# Pipe_flow_header_v3.net
KiCad netlist of a schematic drawn in EAGLE
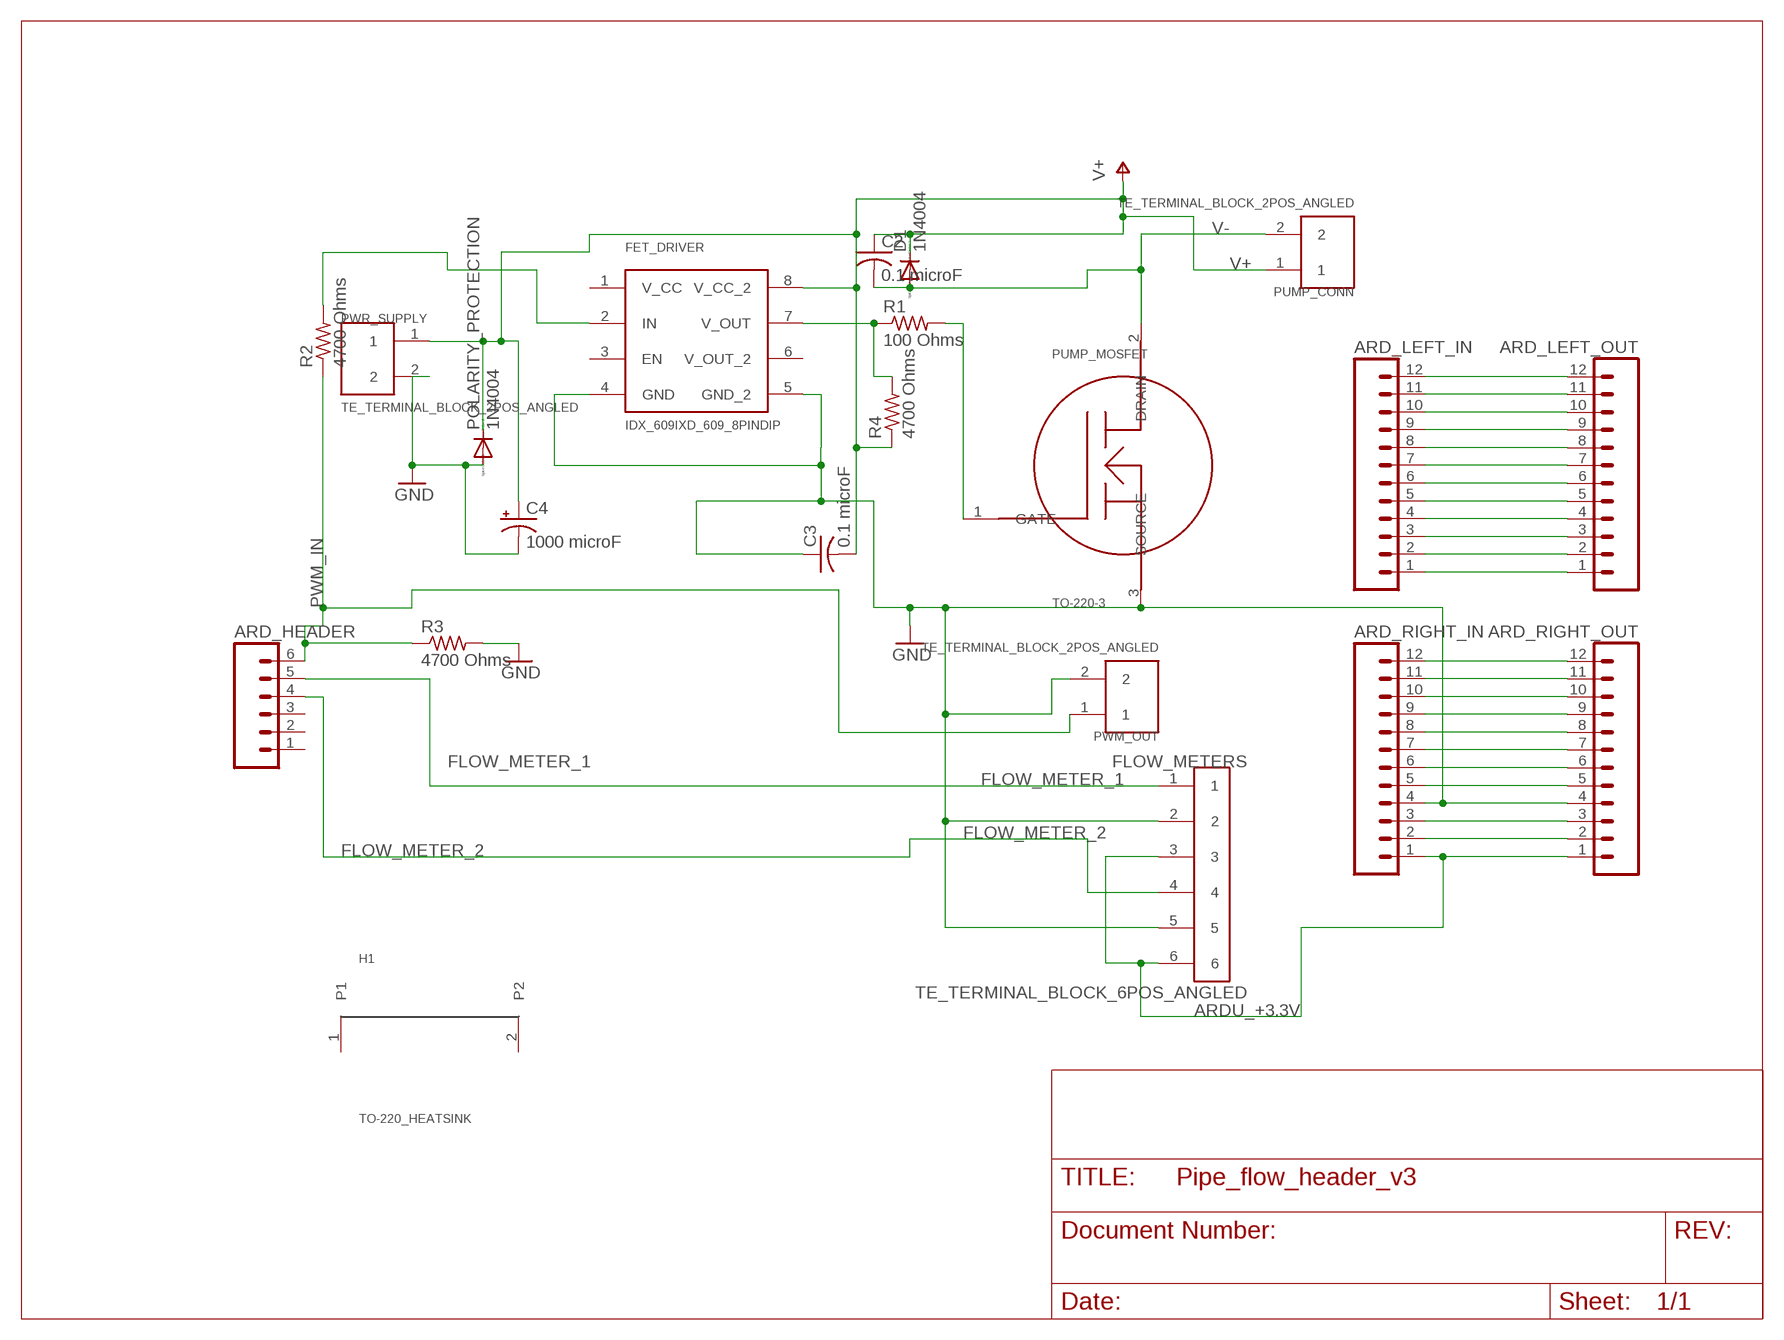
[diagram p0: schematic, sheet 1]

(export (version "E")
  (design (tool "Eeschema 10.0.6"))
  (components
    (comp (ref "ARD_HEADER")
      (value "M06LONGPADS")
      (footprint "eagle-import:1X06_LONGPADS")
      (libsource (lib "eagle-import") (part "M06LONGPADS"))
    )
    (comp (ref "ARD_LEFT_IN")
      (value "M12LOCK_LONGPADS")
      (footprint "eagle-import:1X12_LOCK_LONGPADS")
      (libsource (lib "eagle-import") (part "M12LOCK_LONGPADS"))
    )
    (comp (ref "ARD_LEFT_OUT")
      (value "M12LOCK_LONGPADS")
      (footprint "eagle-import:1X12_LOCK_LONGPADS")
      (libsource (lib "eagle-import") (part "M12LOCK_LONGPADS"))
    )
    (comp (ref "ARD_RIGHT_IN")
      (value "M12LOCK_LONGPADS")
      (footprint "eagle-import:1X12_LOCK_LONGPADS")
      (libsource (lib "eagle-import") (part "M12LOCK_LONGPADS"))
    )
    (comp (ref "ARD_RIGHT_OUT")
      (value "M12LOCK_LONGPADS")
      (footprint "eagle-import:1X12_LOCK_LONGPADS")
      (libsource (lib "eagle-import") (part "M12LOCK_LONGPADS"))
    )
    (comp (ref "C2")
      (value "0.1 microF")
      (footprint "eagle-import:C075-032X103")
      (libsource (lib "eagle-import") (part "C-US075-032X103"))
    )
    (comp (ref "C3")
      (value "0.1 microF")
      (footprint "eagle-import:C075-032X103")
      (libsource (lib "eagle-import") (part "C-US075-032X103"))
    )
    (comp (ref "C4")
      (value "1000 microF")
      (footprint "eagle-import:E7,5-16")
      (libsource (lib "eagle-import") (part "CPOL-USE7.5-16"))
    )
    (comp (ref "D1")
      (value "1N4004")
      (footprint "eagle-import:DO41-10")
      (libsource (lib "eagle-import") (part "1N4004"))
    )
    (comp (ref "FET_DRIVER")
      (value "IDX_609IXD_609_8PINDIP")
      (footprint "eagle-import:IDX_609_8PINDIP")
      (libsource (lib "eagle-import") (part "IDX_609IXD_609_8PINDIP"))
    )
    (comp (ref "FLOW_METERS")
      (value "TE_TERMINAL_BLOCK_6POS_ANGLED")
      (footprint "eagle-import:TE_TERMINAL_BLOCK_6POS_ANGLED")
      (libsource (lib "eagle-import") (part "TE_TERMINAL_BLOCK_6POS_ANGLED"))
    )
    (comp (ref "H1")
      (value "TO-220_HEATSINK")
      (footprint "eagle-import:TO-220_HEATSINK")
      (libsource (lib "eagle-import") (part "TO-220_HEATSINK"))
    )
    (comp (ref "POLARITY_PROTECTION")
      (value "1N4004")
      (footprint "eagle-import:DO41-10")
      (libsource (lib "eagle-import") (part "1N4004"))
    )
    (comp (ref "PUMP_CONN")
      (value "TE_TERMINAL_BLOCK_2POS_ANGLED")
      (footprint "eagle-import:TE_TERMINAL_BLOCK_2POS_ANGLED")
      (libsource (lib "eagle-import") (part "TE_TERMINAL_BLOCK_2POS_ANGLED"))
    )
    (comp (ref "PUMP_MOSFET")
      (value "TO-220-3")
      (footprint "eagle-import:TO-220-3")
      (libsource (lib "eagle-import") (part "TO-220-3"))
    )
    (comp (ref "PWM_OUT")
      (value "TE_TERMINAL_BLOCK_2POS_ANGLED")
      (footprint "eagle-import:TE_TERMINAL_BLOCK_2POS_ANGLED")
      (libsource (lib "eagle-import") (part "TE_TERMINAL_BLOCK_2POS_ANGLED"))
    )
    (comp (ref "PWR_SUPPLY")
      (value "TE_TERMINAL_BLOCK_2POS_ANGLED")
      (footprint "eagle-import:TE_TERMINAL_BLOCK_2POS_ANGLED")
      (libsource (lib "eagle-import") (part "TE_TERMINAL_BLOCK_2POS_ANGLED"))
    )
    (comp (ref "R1")
      (value "100 Ohms")
      (footprint "eagle-import:0204_7")
      (libsource (lib "eagle-import") (part "R-US_0204/7"))
    )
    (comp (ref "R2")
      (value "4700 Ohms")
      (footprint "eagle-import:0204_7")
      (libsource (lib "eagle-import") (part "R-US_0204/7"))
    )
    (comp (ref "R3")
      (value "4700 Ohms")
      (footprint "eagle-import:0204_7")
      (libsource (lib "eagle-import") (part "R-US_0204/7"))
    )
    (comp (ref "R4")
      (value "4700 Ohms")
      (footprint "eagle-import:0204_7")
      (libsource (lib "eagle-import") (part "R-US_0204/7"))
    )
  )
  (nets
    (net (code "1") (name "/ARDU_+3.3V") (class "Default")
      (node (ref "ARD_RIGHT_IN") (pin "1") (pinfunction "1_1") (pintype "passive"))
      (node (ref "ARD_RIGHT_OUT") (pin "1") (pinfunction "1_1") (pintype "passive"))
      (node (ref "FLOW_METERS") (pin "3") (pinfunction "3_3") (pintype "bidirectional"))
      (node (ref "FLOW_METERS") (pin "6") (pinfunction "6_6") (pintype "bidirectional"))
    )
    (net (code "2") (name "/FLOW_METER_1") (class "Default")
      (node (ref "ARD_HEADER") (pin "5") (pinfunction "5_5") (pintype "passive"))
      (node (ref "FLOW_METERS") (pin "1") (pinfunction "1_1") (pintype "bidirectional"))
    )
    (net (code "3") (name "/FLOW_METER_2") (class "Default")
      (node (ref "ARD_HEADER") (pin "4") (pinfunction "4_4") (pintype "passive"))
      (node (ref "FLOW_METERS") (pin "4") (pinfunction "4_4") (pintype "bidirectional"))
    )
    (net (code "4") (name "/PWM_IN") (class "Default")
      (node (ref "ARD_HEADER") (pin "6") (pinfunction "6_6") (pintype "passive"))
      (node (ref "PWM_OUT") (pin "1") (pinfunction "1_1") (pintype "bidirectional"))
      (node (ref "R2") (pin "1") (pinfunction "1_1") (pintype "passive"))
      (node (ref "R3") (pin "1") (pinfunction "1_1") (pintype "passive"))
    )
    (net (code "5") (name "/V-") (class "Default")
      (node (ref "C2") (pin "2") (pinfunction "2_2") (pintype "passive"))
      (node (ref "D1") (pin "A") (pinfunction "A_A") (pintype "passive"))
      (node (ref "PUMP_CONN") (pin "2") (pinfunction "2_2") (pintype "bidirectional"))
      (node (ref "PUMP_MOSFET") (pin "2") (pinfunction "DRAIN_2") (pintype "bidirectional"))
    )
    (net (code "6") (name "GND") (class "Default")
      (node (ref "ARD_RIGHT_IN") (pin "4") (pinfunction "4_4") (pintype "passive"))
      (node (ref "ARD_RIGHT_OUT") (pin "4") (pinfunction "4_4") (pintype "passive"))
      (node (ref "C3") (pin "1") (pinfunction "1_1") (pintype "passive"))
      (node (ref "C4") (pin "-") (pinfunction "-_-") (pintype "passive"))
      (node (ref "FET_DRIVER") (pin "4") (pinfunction "GND_4") (pintype "bidirectional"))
      (node (ref "FET_DRIVER") (pin "5") (pinfunction "GND_2_5") (pintype "bidirectional"))
      (node (ref "FLOW_METERS") (pin "2") (pinfunction "2_2") (pintype "bidirectional"))
      (node (ref "FLOW_METERS") (pin "5") (pinfunction "5_5") (pintype "bidirectional"))
      (node (ref "POLARITY_PROTECTION") (pin "A") (pinfunction "A_A") (pintype "passive"))
      (node (ref "PUMP_MOSFET") (pin "3") (pinfunction "SOURCE_3") (pintype "bidirectional"))
      (node (ref "PWM_OUT") (pin "2") (pinfunction "2_2") (pintype "bidirectional"))
      (node (ref "PWR_SUPPLY") (pin "2") (pinfunction "2_2") (pintype "bidirectional"))
      (node (ref "R3") (pin "2") (pinfunction "2_2") (pintype "passive"))
    )
    (net (code "7") (name "Net-(ARD_LEFT_IN-Pad1)") (class "Default")
      (node (ref "ARD_LEFT_IN") (pin "1") (pinfunction "1_1") (pintype "passive"))
      (node (ref "ARD_LEFT_OUT") (pin "1") (pinfunction "1_1") (pintype "passive"))
    )
    (net (code "8") (name "Net-(ARD_LEFT_IN-Pad2)") (class "Default")
      (node (ref "ARD_LEFT_IN") (pin "2") (pinfunction "2_2") (pintype "passive"))
      (node (ref "ARD_LEFT_OUT") (pin "2") (pinfunction "2_2") (pintype "passive"))
    )
    (net (code "9") (name "Net-(ARD_LEFT_IN-Pad3)") (class "Default")
      (node (ref "ARD_LEFT_IN") (pin "3") (pinfunction "3_3") (pintype "passive"))
      (node (ref "ARD_LEFT_OUT") (pin "3") (pinfunction "3_3") (pintype "passive"))
    )
    (net (code "10") (name "Net-(ARD_LEFT_IN-Pad4)") (class "Default")
      (node (ref "ARD_LEFT_IN") (pin "4") (pinfunction "4_4") (pintype "passive"))
      (node (ref "ARD_LEFT_OUT") (pin "4") (pinfunction "4_4") (pintype "passive"))
    )
    (net (code "11") (name "Net-(ARD_LEFT_IN-Pad5)") (class "Default")
      (node (ref "ARD_LEFT_IN") (pin "5") (pinfunction "5_5") (pintype "passive"))
      (node (ref "ARD_LEFT_OUT") (pin "5") (pinfunction "5_5") (pintype "passive"))
    )
    (net (code "12") (name "Net-(ARD_LEFT_IN-Pad6)") (class "Default")
      (node (ref "ARD_LEFT_IN") (pin "6") (pinfunction "6_6") (pintype "passive"))
      (node (ref "ARD_LEFT_OUT") (pin "6") (pinfunction "6_6") (pintype "passive"))
    )
    (net (code "13") (name "Net-(ARD_LEFT_IN-Pad7)") (class "Default")
      (node (ref "ARD_LEFT_IN") (pin "7") (pinfunction "7_7") (pintype "passive"))
      (node (ref "ARD_LEFT_OUT") (pin "7") (pinfunction "7_7") (pintype "passive"))
    )
    (net (code "14") (name "Net-(ARD_LEFT_IN-Pad8)") (class "Default")
      (node (ref "ARD_LEFT_IN") (pin "8") (pinfunction "8_8") (pintype "passive"))
      (node (ref "ARD_LEFT_OUT") (pin "8") (pinfunction "8_8") (pintype "passive"))
    )
    (net (code "15") (name "Net-(ARD_LEFT_IN-Pad9)") (class "Default")
      (node (ref "ARD_LEFT_IN") (pin "9") (pinfunction "9_9") (pintype "passive"))
      (node (ref "ARD_LEFT_OUT") (pin "9") (pinfunction "9_9") (pintype "passive"))
    )
    (net (code "16") (name "Net-(ARD_LEFT_IN-Pad10)") (class "Default")
      (node (ref "ARD_LEFT_IN") (pin "10") (pinfunction "10_10") (pintype "passive"))
      (node (ref "ARD_LEFT_OUT") (pin "10") (pinfunction "10_10") (pintype "passive"))
    )
    (net (code "17") (name "Net-(ARD_LEFT_IN-Pad11)") (class "Default")
      (node (ref "ARD_LEFT_IN") (pin "11") (pinfunction "11_11") (pintype "passive"))
      (node (ref "ARD_LEFT_OUT") (pin "11") (pinfunction "11_11") (pintype "passive"))
    )
    (net (code "18") (name "Net-(ARD_LEFT_IN-Pad12)") (class "Default")
      (node (ref "ARD_LEFT_IN") (pin "12") (pinfunction "12_12") (pintype "passive"))
      (node (ref "ARD_LEFT_OUT") (pin "12") (pinfunction "12_12") (pintype "passive"))
    )
    (net (code "19") (name "Net-(ARD_RIGHT_IN-Pad2)") (class "Default")
      (node (ref "ARD_RIGHT_IN") (pin "2") (pinfunction "2_2") (pintype "passive"))
      (node (ref "ARD_RIGHT_OUT") (pin "2") (pinfunction "2_2") (pintype "passive"))
    )
    (net (code "20") (name "Net-(ARD_RIGHT_IN-Pad3)") (class "Default")
      (node (ref "ARD_RIGHT_IN") (pin "3") (pinfunction "3_3") (pintype "passive"))
      (node (ref "ARD_RIGHT_OUT") (pin "3") (pinfunction "3_3") (pintype "passive"))
    )
    (net (code "21") (name "Net-(ARD_RIGHT_IN-Pad5)") (class "Default")
      (node (ref "ARD_RIGHT_IN") (pin "5") (pinfunction "5_5") (pintype "passive"))
      (node (ref "ARD_RIGHT_OUT") (pin "5") (pinfunction "5_5") (pintype "passive"))
    )
    (net (code "22") (name "Net-(ARD_RIGHT_IN-Pad6)") (class "Default")
      (node (ref "ARD_RIGHT_IN") (pin "6") (pinfunction "6_6") (pintype "passive"))
      (node (ref "ARD_RIGHT_OUT") (pin "6") (pinfunction "6_6") (pintype "passive"))
    )
    (net (code "23") (name "Net-(ARD_RIGHT_IN-Pad7)") (class "Default")
      (node (ref "ARD_RIGHT_IN") (pin "7") (pinfunction "7_7") (pintype "passive"))
      (node (ref "ARD_RIGHT_OUT") (pin "7") (pinfunction "7_7") (pintype "passive"))
    )
    (net (code "24") (name "Net-(ARD_RIGHT_IN-Pad8)") (class "Default")
      (node (ref "ARD_RIGHT_IN") (pin "8") (pinfunction "8_8") (pintype "passive"))
      (node (ref "ARD_RIGHT_OUT") (pin "8") (pinfunction "8_8") (pintype "passive"))
    )
    (net (code "25") (name "Net-(ARD_RIGHT_IN-Pad9)") (class "Default")
      (node (ref "ARD_RIGHT_IN") (pin "9") (pinfunction "9_9") (pintype "passive"))
      (node (ref "ARD_RIGHT_OUT") (pin "9") (pinfunction "9_9") (pintype "passive"))
    )
    (net (code "26") (name "Net-(ARD_RIGHT_IN-Pad10)") (class "Default")
      (node (ref "ARD_RIGHT_IN") (pin "10") (pinfunction "10_10") (pintype "passive"))
      (node (ref "ARD_RIGHT_OUT") (pin "10") (pinfunction "10_10") (pintype "passive"))
    )
    (net (code "27") (name "Net-(ARD_RIGHT_IN-Pad11)") (class "Default")
      (node (ref "ARD_RIGHT_IN") (pin "11") (pinfunction "11_11") (pintype "passive"))
      (node (ref "ARD_RIGHT_OUT") (pin "11") (pinfunction "11_11") (pintype "passive"))
    )
    (net (code "28") (name "Net-(ARD_RIGHT_IN-Pad12)") (class "Default")
      (node (ref "ARD_RIGHT_IN") (pin "12") (pinfunction "12_12") (pintype "passive"))
      (node (ref "ARD_RIGHT_OUT") (pin "12") (pinfunction "12_12") (pintype "passive"))
    )
    (net (code "29") (name "Net-(FET_DRIVER-IN)") (class "Default")
      (node (ref "FET_DRIVER") (pin "2") (pinfunction "IN_2") (pintype "bidirectional"))
      (node (ref "R2") (pin "2") (pinfunction "2_2") (pintype "passive"))
    )
    (net (code "30") (name "Net-(FET_DRIVER-V_OUT)") (class "Default")
      (node (ref "FET_DRIVER") (pin "7") (pinfunction "V_OUT_7") (pintype "bidirectional"))
      (node (ref "R1") (pin "1") (pinfunction "1_1") (pintype "passive"))
      (node (ref "R4") (pin "2") (pinfunction "2_2") (pintype "passive"))
    )
    (net (code "31") (name "Net-(PUMP_MOSFET-GATE)") (class "Default")
      (node (ref "PUMP_MOSFET") (pin "1") (pinfunction "GATE_1") (pintype "bidirectional"))
      (node (ref "R1") (pin "2") (pinfunction "2_2") (pintype "passive"))
    )
    (net (code "32") (name "V+") (class "Default")
      (node (ref "C2") (pin "1") (pinfunction "1_1") (pintype "passive"))
      (node (ref "C3") (pin "2") (pinfunction "2_2") (pintype "passive"))
      (node (ref "C4") (pin "+") (pinfunction "+_+") (pintype "passive"))
      (node (ref "D1") (pin "C") (pinfunction "C_C") (pintype "passive"))
      (node (ref "FET_DRIVER") (pin "8") (pinfunction "V_CC_2_8") (pintype "bidirectional"))
      (node (ref "POLARITY_PROTECTION") (pin "C") (pinfunction "C_C") (pintype "passive"))
      (node (ref "PUMP_CONN") (pin "1") (pinfunction "1_1") (pintype "bidirectional"))
      (node (ref "PWR_SUPPLY") (pin "1") (pinfunction "1_1") (pintype "bidirectional"))
      (node (ref "R4") (pin "1") (pinfunction "1_1") (pintype "passive"))
    )
    (net (code "33") (name "unconnected-(ARD_HEADER-Pad1)") (class "Default")
      (node (ref "ARD_HEADER") (pin "1") (pinfunction "1_1") (pintype "passive"))
    )
    (net (code "34") (name "unconnected-(ARD_HEADER-Pad2)") (class "Default")
      (node (ref "ARD_HEADER") (pin "2") (pinfunction "2_2") (pintype "passive"))
    )
    (net (code "35") (name "unconnected-(ARD_HEADER-Pad3)") (class "Default")
      (node (ref "ARD_HEADER") (pin "3") (pinfunction "3_3") (pintype "passive"))
    )
    (net (code "36") (name "unconnected-(FET_DRIVER-EN-Pad3)") (class "Default")
      (node (ref "FET_DRIVER") (pin "3") (pinfunction "EN_3") (pintype "bidirectional"))
    )
    (net (code "37") (name "unconnected-(FET_DRIVER-V_CC-Pad1)") (class "Default")
      (node (ref "FET_DRIVER") (pin "1") (pinfunction "V_CC_1") (pintype "bidirectional"))
    )
    (net (code "38") (name "unconnected-(FET_DRIVER-V_OUT_2-Pad6)") (class "Default")
      (node (ref "FET_DRIVER") (pin "6") (pinfunction "V_OUT_2_6") (pintype "bidirectional"))
    )
    (net (code "39") (name "unconnected-(H1-P1-Pad1)") (class "Default")
      (node (ref "H1") (pin "1") (pinfunction "P1_1") (pintype "bidirectional"))
    )
    (net (code "40") (name "unconnected-(H1-P2-Pad2)") (class "Default")
      (node (ref "H1") (pin "2") (pinfunction "P2_2") (pintype "bidirectional"))
    )
  )
)
